# Ant.net
KiCad netlist of a schematic drawn in Altium Designer
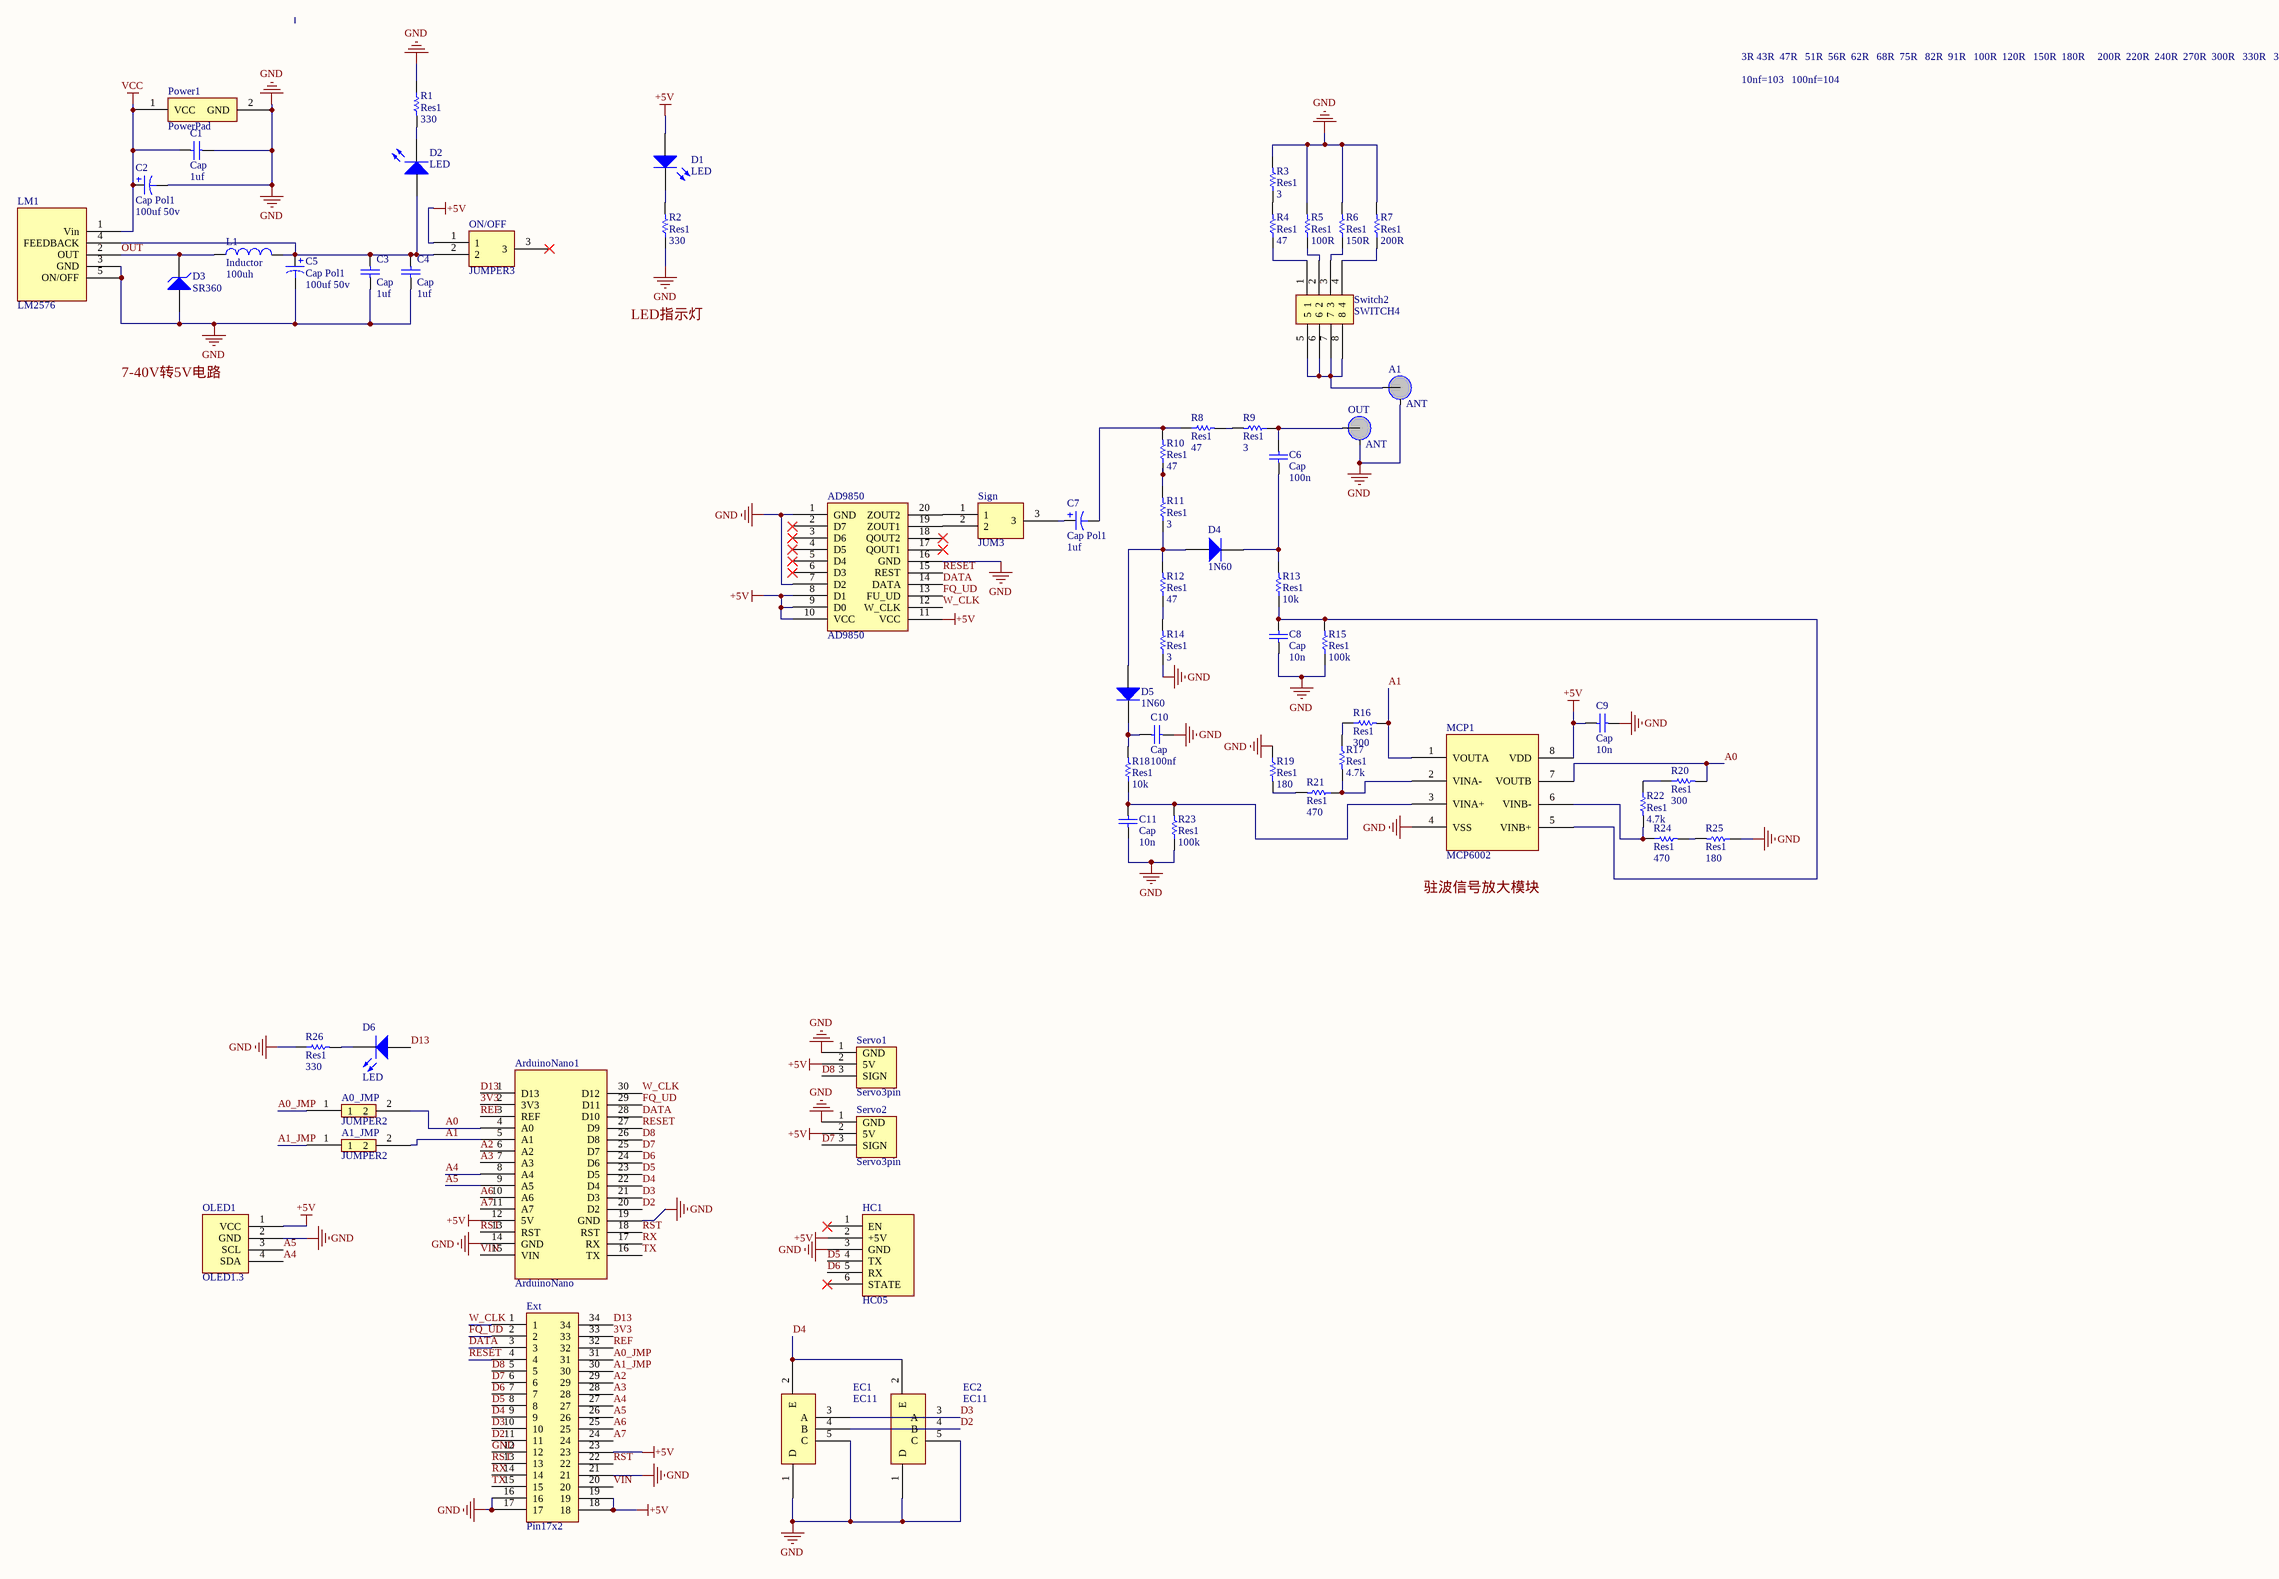
[diagram p0: Ant.SchDoc]

(export (version "E")
  (design (tool "Eeschema 10.0.6"))
  (components
    (comp (ref "A0_JMP") (value "JUMPER2") (footprint "PIN2") (libsource (lib "Ant") (part "JUMPER2")))
    (comp (ref "A1") (value "ANT") (footprint "SMA") (libsource (lib "Ant") (part "ANT")))
    (comp (ref "A1_JMP") (value "JUMPER2") (footprint "PIN2") (libsource (lib "Ant") (part "JUMPER2")))
    (comp (ref "AD9850") (value "AD9850") (footprint "AD9850") (libsource (lib "Ant") (part "AD9850")))
    (comp (ref "ArduinoNano1")
      (value "ArduinoNano")
      (footprint "ArduinoNano")
      (libsource (lib "Ant") (part "ArduinoNano"))
    )
    (comp (ref "C1")
      (value "Cap")
      (footprint "C0805")
      (description "Capacitor")
      (fields (field (name "ALTIUM_VALUE") "1uf") (field (name "PUBLISHER") "Altium Limited"))
      (libsource (lib "Miscellaneous Devices") (part "Cap"))
    )
    (comp (ref "C2")
      (value "Cap Pol1")
      (footprint "C08105")
      (description "Polarized Capacitor (Radial)")
      (fields (field (name "ALTIUM_VALUE") "100uf 50v") (field (name "PUBLISHER") "Altium Limited"))
      (libsource (lib "Miscellaneous Devices") (part "Cap Pol1"))
    )
    (comp (ref "C3")
      (value "Cap")
      (footprint "C0805")
      (description "Capacitor")
      (fields (field (name "ALTIUM_VALUE") "1uf") (field (name "PUBLISHER") "Altium Limited"))
      (libsource (lib "Miscellaneous Devices") (part "Cap"))
    )
    (comp (ref "C4")
      (value "Cap")
      (footprint "C0805")
      (description "Capacitor")
      (fields (field (name "ALTIUM_VALUE") "1uf") (field (name "PUBLISHER") "Altium Limited"))
      (libsource (lib "Miscellaneous Devices") (part "Cap"))
    )
    (comp (ref "C5")
      (value "Cap Pol1")
      (footprint "C08105")
      (description "Polarized Capacitor (Radial)")
      (fields (field (name "ALTIUM_VALUE") "100uf 50v") (field (name "PUBLISHER") "Altium Limited"))
      (libsource (lib "Miscellaneous Devices") (part "Cap Pol1"))
    )
    (comp (ref "C6")
      (value "Cap")
      (footprint "C1206")
      (description "Capacitor")
      (fields (field (name "ALTIUM_VALUE") "100n") (field (name "PUBLISHER") "Altium Limited"))
      (libsource (lib "Miscellaneous Devices") (part "Cap"))
    )
    (comp (ref "C7")
      (value "Cap Pol1")
      (footprint "C5X5.4")
      (description "Polarized Capacitor (Radial)")
      (fields (field (name "ALTIUM_VALUE") "1uf") (field (name "PUBLISHER") "Altium Limited"))
      (libsource (lib "Miscellaneous Devices") (part "Cap Pol1"))
    )
    (comp (ref "C8")
      (value "Cap")
      (footprint "C1206")
      (description "Capacitor")
      (fields (field (name "ALTIUM_VALUE") "10n") (field (name "PUBLISHER") "Altium Limited"))
      (libsource (lib "Miscellaneous Devices") (part "Cap"))
    )
    (comp (ref "C9")
      (value "Cap")
      (footprint "C1206")
      (description "Capacitor")
      (fields (field (name "ALTIUM_VALUE") "10n") (field (name "PUBLISHER") "Altium Limited"))
      (libsource (lib "Miscellaneous Devices") (part "Cap"))
    )
    (comp (ref "C10")
      (value "Cap")
      (footprint "C1206")
      (description "Capacitor")
      (fields (field (name "ALTIUM_VALUE") "100nf") (field (name "PUBLISHER") "Altium Limited"))
      (libsource (lib "Miscellaneous Devices") (part "Cap"))
    )
    (comp (ref "C11")
      (value "Cap")
      (footprint "C1206")
      (description "Capacitor")
      (fields (field (name "ALTIUM_VALUE") "10n") (field (name "PUBLISHER") "Altium Limited"))
      (libsource (lib "Miscellaneous Devices") (part "Cap"))
    )
    (comp (ref "D1")
      (value "LED")
      (footprint "LED0805")
      (description "Typical INFRARED GaAs LED")
      (fields (field (name "PUBLISHER") "Altium Limited"))
      (libsource (lib "Miscellaneous Devices") (part "LED0"))
    )
    (comp (ref "D2")
      (value "LED")
      (footprint "LED0805")
      (description "Typical INFRARED GaAs LED")
      (fields (field (name "PUBLISHER") "Altium Limited"))
      (libsource (lib "Miscellaneous Devices") (part "LED0"))
    )
    (comp (ref "D3")
      (value "SR360")
      (footprint "SR360")
      (description "Zener Diode")
      (fields (field (name "PUBLISHER") "Altium Limited"))
      (libsource (lib "Miscellaneous Devices") (part "D Zener"))
    )
    (comp (ref "D4")
      (value "1N60")
      (footprint "1N60")
      (description "Default Diode")
      (fields (field (name "PUBLISHER") "Altium Limited"))
      (libsource (lib "Miscellaneous Devices") (part "Diode"))
    )
    (comp (ref "D5")
      (value "1N60")
      (footprint "1N60")
      (description "Default Diode")
      (fields (field (name "PUBLISHER") "Altium Limited"))
      (libsource (lib "Miscellaneous Devices") (part "Diode"))
    )
    (comp (ref "D6")
      (value "LED")
      (footprint "LED0805")
      (description "Typical INFRARED GaAs LED")
      (fields (field (name "PUBLISHER") "Altium Limited"))
      (libsource (lib "Miscellaneous Devices") (part "LED0"))
    )
    (comp (ref "EC1") (value "EC11") (footprint "PIN5") (libsource (lib "Ant") (part "EC11")))
    (comp (ref "EC2") (value "EC11") (footprint "EC11") (libsource (lib "Ant") (part "EC11")))
    (comp (ref "Ext") (value "Pin17x2") (footprint "Pin17x2") (libsource (lib "Ant") (part "Pin17x2")))
    (comp (ref "HC1") (value "HC05") (footprint "PIN6") (libsource (lib "Ant") (part "HC05")))
    (comp (ref "L1")
      (value "Inductor")
      (footprint "L12127")
      (fields (field (name "ALTIUM_VALUE") "100uh") (field (name "PUBLISHER") "Altium Limited"))
      (libsource (lib "Miscellaneous Devices") (part "Inductor"))
    )
    (comp (ref "LM1") (value "LM2576") (libsource (lib "Ant") (part "LM2576")))
    (comp (ref "MCP1") (value "MCP6002") (footprint "MCP6002") (libsource (lib "Ant") (part "MCP6002")))
    (comp (ref "OLED1") (value "OLED1.3") (footprint "PIN4") (libsource (lib "Ant") (part "OLED1.3")))
    (comp (ref "ON/OFF") (value "JUMPER3") (footprint "SWITCH") (libsource (lib "Ant") (part "JUMPER3")))
    (comp (ref "OUT") (value "ANT") (footprint "PAD2") (libsource (lib "Ant") (part "ANT")))
    (comp (ref "Power1") (value "PowerPad") (footprint "Power3pin") (libsource (lib "Ant") (part "PowerPad")))
    (comp (ref "R1")
      (value "Res1")
      (footprint "r0805")
      (description "Resistor")
      (fields (field (name "ALTIUM_VALUE") "330") (field (name "PUBLISHER") "Altium Limited"))
      (libsource (lib "Miscellaneous Devices") (part "Res1"))
    )
    (comp (ref "R2")
      (value "Res1")
      (footprint "r0805")
      (description "Resistor")
      (fields (field (name "ALTIUM_VALUE") "330") (field (name "PUBLISHER") "Altium Limited"))
      (libsource (lib "Miscellaneous Devices") (part "Res1"))
    )
    (comp (ref "R3")
      (value "Res1")
      (footprint "R1206")
      (description "Resistor")
      (fields (field (name "ALTIUM_VALUE") "3") (field (name "PUBLISHER") "Altium Limited"))
      (libsource (lib "Miscellaneous Devices") (part "Res1"))
    )
    (comp (ref "R4")
      (value "Res1")
      (footprint "R1206")
      (description "Resistor")
      (fields (field (name "ALTIUM_VALUE") "47") (field (name "PUBLISHER") "Altium Limited"))
      (libsource (lib "Miscellaneous Devices") (part "Res1"))
    )
    (comp (ref "R5")
      (value "Res1")
      (footprint "R1206")
      (description "Resistor")
      (fields (field (name "ALTIUM_VALUE") "100R") (field (name "PUBLISHER") "Altium Limited"))
      (libsource (lib "Miscellaneous Devices") (part "Res1"))
    )
    (comp (ref "R6")
      (value "Res1")
      (footprint "R1206")
      (description "Resistor")
      (fields (field (name "ALTIUM_VALUE") "150R") (field (name "PUBLISHER") "Altium Limited"))
      (libsource (lib "Miscellaneous Devices") (part "Res1"))
    )
    (comp (ref "R7")
      (value "Res1")
      (footprint "R1206")
      (description "Resistor")
      (fields (field (name "ALTIUM_VALUE") "200R") (field (name "PUBLISHER") "Altium Limited"))
      (libsource (lib "Miscellaneous Devices") (part "Res1"))
    )
    (comp (ref "R8")
      (value "Res1")
      (footprint "R1206")
      (description "Resistor")
      (fields (field (name "ALTIUM_VALUE") "47") (field (name "PUBLISHER") "Altium Limited"))
      (libsource (lib "Miscellaneous Devices") (part "Res1"))
    )
    (comp (ref "R9")
      (value "Res1")
      (footprint "R1206")
      (description "Resistor")
      (fields (field (name "ALTIUM_VALUE") "3") (field (name "PUBLISHER") "Altium Limited"))
      (libsource (lib "Miscellaneous Devices") (part "Res1"))
    )
    (comp (ref "R10")
      (value "Res1")
      (footprint "R1206")
      (description "Resistor")
      (fields (field (name "ALTIUM_VALUE") "47") (field (name "PUBLISHER") "Altium Limited"))
      (libsource (lib "Miscellaneous Devices") (part "Res1"))
    )
    (comp (ref "R11")
      (value "Res1")
      (footprint "R1206")
      (description "Resistor")
      (fields (field (name "ALTIUM_VALUE") "3") (field (name "PUBLISHER") "Altium Limited"))
      (libsource (lib "Miscellaneous Devices") (part "Res1"))
    )
    (comp (ref "R12")
      (value "Res1")
      (footprint "R1206")
      (description "Resistor")
      (fields (field (name "ALTIUM_VALUE") "47") (field (name "PUBLISHER") "Altium Limited"))
      (libsource (lib "Miscellaneous Devices") (part "Res1"))
    )
    (comp (ref "R13")
      (value "Res1")
      (footprint "R1206")
      (description "Resistor")
      (fields (field (name "ALTIUM_VALUE") "10k") (field (name "PUBLISHER") "Altium Limited"))
      (libsource (lib "Miscellaneous Devices") (part "Res1"))
    )
    (comp (ref "R14")
      (value "Res1")
      (footprint "R1206")
      (description "Resistor")
      (fields (field (name "ALTIUM_VALUE") "3") (field (name "PUBLISHER") "Altium Limited"))
      (libsource (lib "Miscellaneous Devices") (part "Res1"))
    )
    (comp (ref "R15")
      (value "Res1")
      (footprint "R1206")
      (description "Resistor")
      (fields (field (name "ALTIUM_VALUE") "100k") (field (name "PUBLISHER") "Altium Limited"))
      (libsource (lib "Miscellaneous Devices") (part "Res1"))
    )
    (comp (ref "R16")
      (value "Res1")
      (footprint "R1206")
      (description "Resistor")
      (fields (field (name "ALTIUM_VALUE") "300") (field (name "PUBLISHER") "Altium Limited"))
      (libsource (lib "Miscellaneous Devices") (part "Res1"))
    )
    (comp (ref "R17")
      (value "Res1")
      (footprint "R1206")
      (description "Resistor")
      (fields (field (name "ALTIUM_VALUE") "4.7k") (field (name "PUBLISHER") "Altium Limited"))
      (libsource (lib "Miscellaneous Devices") (part "Res1"))
    )
    (comp (ref "R18")
      (value "Res1")
      (footprint "R1206")
      (description "Resistor")
      (fields (field (name "ALTIUM_VALUE") "10k") (field (name "PUBLISHER") "Altium Limited"))
      (libsource (lib "Miscellaneous Devices") (part "Res1"))
    )
    (comp (ref "R19")
      (value "Res1")
      (footprint "R1206")
      (description "Resistor")
      (fields (field (name "ALTIUM_VALUE") "180") (field (name "PUBLISHER") "Altium Limited"))
      (libsource (lib "Miscellaneous Devices") (part "Res1"))
    )
    (comp (ref "R20")
      (value "Res1")
      (footprint "R1206")
      (description "Resistor")
      (fields (field (name "ALTIUM_VALUE") "300") (field (name "PUBLISHER") "Altium Limited"))
      (libsource (lib "Miscellaneous Devices") (part "Res1"))
    )
    (comp (ref "R21")
      (value "Res1")
      (footprint "R1206")
      (description "Resistor")
      (fields (field (name "ALTIUM_VALUE") "470") (field (name "PUBLISHER") "Altium Limited"))
      (libsource (lib "Miscellaneous Devices") (part "Res1"))
    )
    (comp (ref "R22")
      (value "Res1")
      (footprint "R1206")
      (description "Resistor")
      (fields (field (name "ALTIUM_VALUE") "4.7k") (field (name "PUBLISHER") "Altium Limited"))
      (libsource (lib "Miscellaneous Devices") (part "Res1"))
    )
    (comp (ref "R23")
      (value "Res1")
      (footprint "R1206")
      (description "Resistor")
      (fields (field (name "ALTIUM_VALUE") "100k") (field (name "PUBLISHER") "Altium Limited"))
      (libsource (lib "Miscellaneous Devices") (part "Res1"))
    )
    (comp (ref "R24")
      (value "Res1")
      (footprint "R1206")
      (description "Resistor")
      (fields (field (name "ALTIUM_VALUE") "470") (field (name "PUBLISHER") "Altium Limited"))
      (libsource (lib "Miscellaneous Devices") (part "Res1"))
    )
    (comp (ref "R25")
      (value "Res1")
      (footprint "R1206")
      (description "Resistor")
      (fields (field (name "ALTIUM_VALUE") "180") (field (name "PUBLISHER") "Altium Limited"))
      (libsource (lib "Miscellaneous Devices") (part "Res1"))
    )
    (comp (ref "R26")
      (value "Res1")
      (footprint "r0805")
      (description "Resistor")
      (fields (field (name "ALTIUM_VALUE") "330") (field (name "PUBLISHER") "Altium Limited"))
      (libsource (lib "Miscellaneous Devices") (part "Res1"))
    )
    (comp (ref "Servo1") (value "Servo3pin") (footprint "PIN3") (libsource (lib "Ant") (part "Servo3pin")))
    (comp (ref "Servo2") (value "Servo3pin") (footprint "PIN3") (libsource (lib "Ant") (part "Servo3pin")))
    (comp (ref "Sign") (value "JUM3") (footprint "SWITCH3") (libsource (lib "Ant") (part "JUM3")))
    (comp (ref "Switch2") (value "SWITCH4") (footprint "SWITCH4") (libsource (lib "Ant") (part "SWITCH4")))
  )
  (nets
    (net (code "1") (name "+5V") (class "Default")
      (node (ref "AD9850") (pin "10") (pinfunction "VCC_10") (pintype "passive"))
      (node (ref "AD9850") (pin "11") (pinfunction "VCC_11") (pintype "passive"))
      (node (ref "AD9850") (pin "8") (pinfunction "D1_8") (pintype "passive"))
      (node (ref "AD9850") (pin "9") (pinfunction "D0_9") (pintype "passive"))
      (node (ref "ArduinoNano1") (pin "12") (pinfunction "5V_12") (pintype "passive"))
      (node (ref "C9") (pin "1") (pinfunction "1_1") (pintype "passive"))
      (node (ref "D1") (pin "1") (pinfunction "A_1") (pintype "passive"))
      (node (ref "Ext") (pin "18") (pinfunction "18_18") (pintype "passive"))
      (node (ref "Ext") (pin "19") (pinfunction "19_19") (pintype "passive"))
      (node (ref "Ext") (pin "23") (pinfunction "23_23") (pintype "passive"))
      (node (ref "HC1") (pin "2") (pinfunction "+5V_2") (pintype "passive"))
      (node (ref "MCP1") (pin "8") (pinfunction "VDD_8") (pintype "passive"))
      (node (ref "OLED1") (pin "1") (pinfunction "VCC_1") (pintype "passive"))
      (node (ref "ON/OFF") (pin "1") (pinfunction "1_1") (pintype "passive"))
      (node (ref "Servo1") (pin "2") (pinfunction "5V_2") (pintype "passive"))
      (node (ref "Servo2") (pin "2") (pinfunction "5V_2") (pintype "passive"))
    )
    (net (code "2") (name "/3V3") (class "Default")
      (node (ref "ArduinoNano1") (pin "2") (pinfunction "3V3_2") (pintype "passive"))
      (node (ref "Ext") (pin "33") (pinfunction "33_33") (pintype "passive"))
    )
    (net (code "3") (name "/A0") (class "Default")
      (node (ref "A0_JMP") (pin "2") (pinfunction "2_2") (pintype "passive"))
      (node (ref "ArduinoNano1") (pin "4") (pinfunction "A0_4") (pintype "passive"))
      (node (ref "MCP1") (pin "7") (pinfunction "VOUTB_7") (pintype "passive"))
      (node (ref "R20") (pin "2") (pinfunction "2_2") (pintype "passive"))
    )
    (net (code "4") (name "/A0_JMP") (class "Default")
      (node (ref "A0_JMP") (pin "1") (pinfunction "1_1") (pintype "passive"))
      (node (ref "Ext") (pin "31") (pinfunction "31_31") (pintype "passive"))
    )
    (net (code "5") (name "/A1") (class "Default")
      (node (ref "A1_JMP") (pin "2") (pinfunction "2_2") (pintype "passive"))
      (node (ref "ArduinoNano1") (pin "5") (pinfunction "A1_5") (pintype "passive"))
      (node (ref "MCP1") (pin "1") (pinfunction "VOUTA_1") (pintype "passive"))
      (node (ref "R16") (pin "2") (pinfunction "2_2") (pintype "passive"))
    )
    (net (code "6") (name "/A1_JMP") (class "Default")
      (node (ref "A1_JMP") (pin "1") (pinfunction "1_1") (pintype "passive"))
      (node (ref "Ext") (pin "30") (pinfunction "30_30") (pintype "passive"))
    )
    (net (code "7") (name "/A2") (class "Default")
      (node (ref "ArduinoNano1") (pin "6") (pinfunction "A2_6") (pintype "passive"))
      (node (ref "Ext") (pin "29") (pinfunction "29_29") (pintype "passive"))
    )
    (net (code "8") (name "/A3") (class "Default")
      (node (ref "ArduinoNano1") (pin "7") (pinfunction "A3_7") (pintype "passive"))
      (node (ref "Ext") (pin "28") (pinfunction "28_28") (pintype "passive"))
    )
    (net (code "9") (name "/A4") (class "Default")
      (node (ref "ArduinoNano1") (pin "8") (pinfunction "A4_8") (pintype "passive"))
      (node (ref "Ext") (pin "27") (pinfunction "27_27") (pintype "passive"))
      (node (ref "OLED1") (pin "4") (pinfunction "SDA_4") (pintype "passive"))
    )
    (net (code "10") (name "/A5") (class "Default")
      (node (ref "ArduinoNano1") (pin "9") (pinfunction "A5_9") (pintype "passive"))
      (node (ref "Ext") (pin "26") (pinfunction "26_26") (pintype "passive"))
      (node (ref "OLED1") (pin "3") (pinfunction "SCL_3") (pintype "passive"))
    )
    (net (code "11") (name "/A6") (class "Default")
      (node (ref "ArduinoNano1") (pin "10") (pinfunction "A6_10") (pintype "passive"))
      (node (ref "Ext") (pin "25") (pinfunction "25_25") (pintype "passive"))
    )
    (net (code "12") (name "/A7") (class "Default")
      (node (ref "ArduinoNano1") (pin "11") (pinfunction "A7_11") (pintype "passive"))
      (node (ref "Ext") (pin "24") (pinfunction "24_24") (pintype "passive"))
    )
    (net (code "13") (name "/D2") (class "Default")
      (node (ref "ArduinoNano1") (pin "20") (pinfunction "D2_20") (pintype "passive"))
      (node (ref "EC1") (pin "4") (pinfunction "B_4") (pintype "passive"))
      (node (ref "EC2") (pin "4") (pinfunction "B_4") (pintype "passive"))
      (node (ref "Ext") (pin "11") (pinfunction "11_11") (pintype "passive"))
    )
    (net (code "14") (name "/D3") (class "Default")
      (node (ref "ArduinoNano1") (pin "21") (pinfunction "D3_21") (pintype "passive"))
      (node (ref "EC1") (pin "3") (pinfunction "A_3") (pintype "passive"))
      (node (ref "EC2") (pin "3") (pinfunction "A_3") (pintype "passive"))
      (node (ref "Ext") (pin "10") (pinfunction "10_10") (pintype "passive"))
    )
    (net (code "15") (name "/D4") (class "Default")
      (node (ref "ArduinoNano1") (pin "22") (pinfunction "D4_22") (pintype "passive"))
      (node (ref "EC1") (pin "2") (pinfunction "E_2") (pintype "passive"))
      (node (ref "EC2") (pin "2") (pinfunction "E_2") (pintype "passive"))
      (node (ref "Ext") (pin "9") (pinfunction "9_9") (pintype "passive"))
    )
    (net (code "16") (name "/D5") (class "Default")
      (node (ref "ArduinoNano1") (pin "23") (pinfunction "D5_23") (pintype "passive"))
      (node (ref "Ext") (pin "8") (pinfunction "8_8") (pintype "passive"))
      (node (ref "HC1") (pin "4") (pinfunction "TX_4") (pintype "passive"))
    )
    (net (code "17") (name "/D6") (class "Default")
      (node (ref "ArduinoNano1") (pin "24") (pinfunction "D6_24") (pintype "passive"))
      (node (ref "Ext") (pin "7") (pinfunction "7_7") (pintype "passive"))
      (node (ref "HC1") (pin "5") (pinfunction "RX_5") (pintype "passive"))
    )
    (net (code "18") (name "/D7") (class "Default")
      (node (ref "ArduinoNano1") (pin "25") (pinfunction "D7_25") (pintype "passive"))
      (node (ref "Ext") (pin "6") (pinfunction "6_6") (pintype "passive"))
      (node (ref "Servo2") (pin "3") (pinfunction "SIGN_3") (pintype "passive"))
    )
    (net (code "19") (name "/D8") (class "Default")
      (node (ref "ArduinoNano1") (pin "26") (pinfunction "D8_26") (pintype "passive"))
      (node (ref "Ext") (pin "5") (pinfunction "5_5") (pintype "passive"))
      (node (ref "Servo1") (pin "3") (pinfunction "SIGN_3") (pintype "passive"))
    )
    (net (code "20") (name "/D13") (class "Default")
      (node (ref "ArduinoNano1") (pin "1") (pinfunction "D13_1") (pintype "passive"))
      (node (ref "D6") (pin "1") (pinfunction "A_1") (pintype "passive"))
      (node (ref "Ext") (pin "34") (pinfunction "34_34") (pintype "passive"))
    )
    (net (code "21") (name "/DATA") (class "Default")
      (node (ref "AD9850") (pin "14") (pinfunction "DATA_14") (pintype "passive"))
      (node (ref "ArduinoNano1") (pin "28") (pinfunction "D10_28") (pintype "passive"))
      (node (ref "Ext") (pin "3") (pinfunction "3_3") (pintype "passive"))
    )
    (net (code "22") (name "/FQ_UD") (class "Default")
      (node (ref "AD9850") (pin "13") (pinfunction "FU_UD_13") (pintype "passive"))
      (node (ref "ArduinoNano1") (pin "29") (pinfunction "D11_29") (pintype "passive"))
      (node (ref "Ext") (pin "2") (pinfunction "2_2") (pintype "passive"))
    )
    (net (code "23") (name "/OUT") (class "Default")
      (node (ref "D3") (pin "2") (pinfunction "K_2") (pintype "passive"))
      (node (ref "L1") (pin "1") (pinfunction "1_1") (pintype "passive"))
      (node (ref "LM1") (pin "2") (pinfunction "OUT_2") (pintype "passive"))
    )
    (net (code "24") (name "/REF") (class "Default")
      (node (ref "ArduinoNano1") (pin "3") (pinfunction "REF_3") (pintype "passive"))
      (node (ref "Ext") (pin "32") (pinfunction "32_32") (pintype "passive"))
    )
    (net (code "25") (name "/RESET") (class "Default")
      (node (ref "AD9850") (pin "15") (pinfunction "REST_15") (pintype "passive"))
      (node (ref "ArduinoNano1") (pin "27") (pinfunction "D9_27") (pintype "passive"))
      (node (ref "Ext") (pin "4") (pinfunction "4_4") (pintype "passive"))
    )
    (net (code "26") (name "/RST") (class "Default")
      (node (ref "ArduinoNano1") (pin "13") (pinfunction "RST_13") (pintype "passive"))
      (node (ref "ArduinoNano1") (pin "18") (pinfunction "RST_18") (pintype "passive"))
      (node (ref "Ext") (pin "13") (pinfunction "13_13") (pintype "passive"))
      (node (ref "Ext") (pin "22") (pinfunction "22_22") (pintype "passive"))
    )
    (net (code "27") (name "/RX") (class "Default")
      (node (ref "ArduinoNano1") (pin "17") (pinfunction "RX_17") (pintype "passive"))
      (node (ref "Ext") (pin "14") (pinfunction "14_14") (pintype "passive"))
    )
    (net (code "28") (name "/TX") (class "Default")
      (node (ref "ArduinoNano1") (pin "16") (pinfunction "TX_16") (pintype "passive"))
      (node (ref "Ext") (pin "15") (pinfunction "15_15") (pintype "passive"))
    )
    (net (code "29") (name "/VIN") (class "Default")
      (node (ref "ArduinoNano1") (pin "15") (pinfunction "VIN_15") (pintype "passive"))
      (node (ref "Ext") (pin "20") (pinfunction "20_20") (pintype "passive"))
    )
    (net (code "30") (name "/W_CLK") (class "Default")
      (node (ref "AD9850") (pin "12") (pinfunction "W_CLK_12") (pintype "passive"))
      (node (ref "ArduinoNano1") (pin "30") (pinfunction "D12_30") (pintype "passive"))
      (node (ref "Ext") (pin "1") (pinfunction "1_1") (pintype "passive"))
    )
    (net (code "31") (name "GND") (class "Default")
      (node (ref "A1") (pin "2") (pintype "passive"))
      (node (ref "AD9850") (pin "1") (pinfunction "GND_1") (pintype "passive"))
      (node (ref "AD9850") (pin "16") (pinfunction "GND_16") (pintype "passive"))
      (node (ref "AD9850") (pin "7") (pinfunction "D2_7") (pintype "passive"))
      (node (ref "ArduinoNano1") (pin "14") (pinfunction "GND_14") (pintype "passive"))
      (node (ref "ArduinoNano1") (pin "19") (pinfunction "GND_19") (pintype "passive"))
      (node (ref "C1") (pin "2") (pinfunction "2_2") (pintype "passive"))
      (node (ref "C10") (pin "2") (pinfunction "2_2") (pintype "passive"))
      (node (ref "C11") (pin "1") (pinfunction "1_1") (pintype "passive"))
      (node (ref "C2") (pin "2") (pinfunction "2_2") (pintype "passive"))
      (node (ref "C3") (pin "2") (pinfunction "2_2") (pintype "passive"))
      (node (ref "C4") (pin "2") (pinfunction "2_2") (pintype "passive"))
      (node (ref "C5") (pin "2") (pinfunction "2_2") (pintype "passive"))
      (node (ref "C8") (pin "2") (pinfunction "2_2") (pintype "passive"))
      (node (ref "C9") (pin "2") (pinfunction "2_2") (pintype "passive"))
      (node (ref "D3") (pin "1") (pinfunction "A_1") (pintype "passive"))
      (node (ref "EC1") (pin "1") (pinfunction "D_1") (pintype "passive"))
      (node (ref "EC1") (pin "5") (pinfunction "C_5") (pintype "passive"))
      (node (ref "EC2") (pin "1") (pinfunction "D_1") (pintype "passive"))
      (node (ref "EC2") (pin "5") (pinfunction "C_5") (pintype "passive"))
      (node (ref "Ext") (pin "12") (pinfunction "12_12") (pintype "passive"))
      (node (ref "Ext") (pin "16") (pinfunction "16_16") (pintype "passive"))
      (node (ref "Ext") (pin "17") (pinfunction "17_17") (pintype "passive"))
      (node (ref "Ext") (pin "21") (pinfunction "21_21") (pintype "passive"))
      (node (ref "HC1") (pin "3") (pinfunction "GND_3") (pintype "passive"))
      (node (ref "LM1") (pin "3") (pinfunction "GND_3") (pintype "passive"))
      (node (ref "LM1") (pin "5") (pinfunction "ON/OFF_5") (pintype "passive"))
      (node (ref "MCP1") (pin "4") (pinfunction "VSS_4") (pintype "passive"))
      (node (ref "OLED1") (pin "2") (pinfunction "GND_2") (pintype "passive"))
      (node (ref "OUT") (pin "2") (pintype "passive"))
      (node (ref "Power1") (pin "2") (pinfunction "GND_2") (pintype "passive"))
      (node (ref "R1") (pin "1") (pinfunction "1_1") (pintype "passive"))
      (node (ref "R14") (pin "1") (pinfunction "1_1") (pintype "passive"))
      (node (ref "R15") (pin "1") (pinfunction "1_1") (pintype "passive"))
      (node (ref "R19") (pin "1") (pinfunction "1_1") (pintype "passive"))
      (node (ref "R2") (pin "1") (pinfunction "1_1") (pintype "passive"))
      (node (ref "R23") (pin "1") (pinfunction "1_1") (pintype "passive"))
      (node (ref "R25") (pin "1") (pinfunction "1_1") (pintype "passive"))
      (node (ref "R26") (pin "1") (pinfunction "1_1") (pintype "passive"))
      (node (ref "R3") (pin "2") (pinfunction "2_2") (pintype "passive"))
      (node (ref "R5") (pin "2") (pinfunction "2_2") (pintype "passive"))
      (node (ref "R6") (pin "2") (pinfunction "2_2") (pintype "passive"))
      (node (ref "R7") (pin "2") (pinfunction "2_2") (pintype "passive"))
      (node (ref "Servo1") (pin "1") (pinfunction "GND_1") (pintype "passive"))
      (node (ref "Servo2") (pin "1") (pinfunction "GND_1") (pintype "passive"))
    )
    (net (code "32") (name "Net-(A1-Pad1)") (class "Default")
      (node (ref "A1") (pin "1") (pintype "passive"))
      (node (ref "Switch2") (pin "5") (pinfunction "5_5") (pintype "passive"))
      (node (ref "Switch2") (pin "6") (pinfunction "6_6") (pintype "passive"))
      (node (ref "Switch2") (pin "7") (pinfunction "7_7") (pintype "passive"))
      (node (ref "Switch2") (pin "8") (pinfunction "8_8") (pintype "passive"))
    )
    (net (code "33") (name "Net-(AD9850-ZOUT1)") (class "Default")
      (node (ref "AD9850") (pin "19") (pinfunction "ZOUT1_19") (pintype "passive"))
      (node (ref "Sign") (pin "2") (pinfunction "2_2") (pintype "passive"))
    )
    (net (code "34") (name "Net-(AD9850-ZOUT2)") (class "Default")
      (node (ref "AD9850") (pin "20") (pinfunction "ZOUT2_20") (pintype "passive"))
      (node (ref "Sign") (pin "1") (pinfunction "1_1") (pintype "passive"))
    )
    (net (code "35") (name "Net-(C6-Pad1)") (class "Default")
      (node (ref "C6") (pin "1") (pinfunction "1_1") (pintype "passive"))
      (node (ref "OUT") (pin "1") (pintype "passive"))
      (node (ref "R9") (pin "1") (pinfunction "1_1") (pintype "passive"))
    )
    (net (code "36") (name "Net-(C7-Pad1)") (class "Default")
      (node (ref "C7") (pin "1") (pinfunction "1_1") (pintype "passive"))
      (node (ref "Sign") (pin "3") (pinfunction "3_3") (pintype "passive"))
    )
    (net (code "37") (name "Net-(C7-Pad2)") (class "Default")
      (node (ref "C7") (pin "2") (pinfunction "2_2") (pintype "passive"))
      (node (ref "R10") (pin "2") (pinfunction "2_2") (pintype "passive"))
      (node (ref "R8") (pin "1") (pinfunction "1_1") (pintype "passive"))
    )
    (net (code "38") (name "Net-(D1-K)") (class "Default")
      (node (ref "D1") (pin "2") (pinfunction "K_2") (pintype "passive"))
      (node (ref "R2") (pin "2") (pinfunction "2_2") (pintype "passive"))
    )
    (net (code "39") (name "Net-(D2-A)") (class "Default")
      (node (ref "C3") (pin "1") (pinfunction "1_1") (pintype "passive"))
      (node (ref "C4") (pin "1") (pinfunction "1_1") (pintype "passive"))
      (node (ref "C5") (pin "1") (pinfunction "1_1") (pintype "passive"))
      (node (ref "D2") (pin "1") (pinfunction "A_1") (pintype "passive"))
      (node (ref "L1") (pin "2") (pinfunction "2_2") (pintype "passive"))
      (node (ref "LM1") (pin "4") (pinfunction "FEEDBACK_4") (pintype "passive"))
      (node (ref "ON/OFF") (pin "2") (pinfunction "2_2") (pintype "passive"))
    )
    (net (code "40") (name "Net-(D2-K)") (class "Default")
      (node (ref "D2") (pin "2") (pinfunction "K_2") (pintype "passive"))
      (node (ref "R1") (pin "2") (pinfunction "2_2") (pintype "passive"))
    )
    (net (code "41") (name "Net-(D4-A)") (class "Default")
      (node (ref "D4") (pin "1") (pinfunction "A_1") (pintype "passive"))
      (node (ref "D5") (pin "1") (pinfunction "A_1") (pintype "passive"))
      (node (ref "R11") (pin "1") (pinfunction "1_1") (pintype "passive"))
      (node (ref "R12") (pin "2") (pinfunction "2_2") (pintype "passive"))
    )
    (net (code "42") (name "Net-(D4-K)") (class "Default")
      (node (ref "C6") (pin "2") (pinfunction "2_2") (pintype "passive"))
      (node (ref "D4") (pin "2") (pinfunction "K_2") (pintype "passive"))
      (node (ref "R13") (pin "2") (pinfunction "2_2") (pintype "passive"))
    )
    (net (code "43") (name "Net-(D5-K)") (class "Default")
      (node (ref "C10") (pin "1") (pinfunction "1_1") (pintype "passive"))
      (node (ref "D5") (pin "2") (pinfunction "K_2") (pintype "passive"))
      (node (ref "R18") (pin "2") (pinfunction "2_2") (pintype "passive"))
    )
    (net (code "44") (name "Net-(D6-K)") (class "Default")
      (node (ref "D6") (pin "2") (pinfunction "K_2") (pintype "passive"))
      (node (ref "R26") (pin "2") (pinfunction "2_2") (pintype "passive"))
    )
    (net (code "45") (name "Net-(MCP1-VINA+)") (class "Default")
      (node (ref "C11") (pin "2") (pinfunction "2_2") (pintype "passive"))
      (node (ref "MCP1") (pin "3") (pinfunction "VINA+_3") (pintype "passive"))
      (node (ref "R18") (pin "1") (pinfunction "1_1") (pintype "passive"))
      (node (ref "R23") (pin "2") (pinfunction "2_2") (pintype "passive"))
    )
    (net (code "46") (name "Net-(MCP1-VINA-)") (class "Default")
      (node (ref "MCP1") (pin "2") (pinfunction "VINA-_2") (pintype "passive"))
      (node (ref "R17") (pin "2") (pinfunction "2_2") (pintype "passive"))
      (node (ref "R21") (pin "1") (pinfunction "1_1") (pintype "passive"))
    )
    (net (code "47") (name "Net-(MCP1-VINB+)") (class "Default")
      (node (ref "C8") (pin "1") (pinfunction "1_1") (pintype "passive"))
      (node (ref "MCP1") (pin "5") (pinfunction "VINB+_5") (pintype "passive"))
      (node (ref "R13") (pin "1") (pinfunction "1_1") (pintype "passive"))
      (node (ref "R15") (pin "2") (pinfunction "2_2") (pintype "passive"))
    )
    (net (code "48") (name "Net-(MCP1-VINB-)") (class "Default")
      (node (ref "MCP1") (pin "6") (pinfunction "VINB-_6") (pintype "passive"))
      (node (ref "R22") (pin "2") (pinfunction "2_2") (pintype "passive"))
      (node (ref "R24") (pin "1") (pinfunction "1_1") (pintype "passive"))
    )
    (net (code "49") (name "Net-(R3-Pad1)") (class "Default")
      (node (ref "R3") (pin "1") (pinfunction "1_1") (pintype "passive"))
      (node (ref "R4") (pin "2") (pinfunction "2_2") (pintype "passive"))
    )
    (net (code "50") (name "Net-(R4-Pad1)") (class "Default")
      (node (ref "R4") (pin "1") (pinfunction "1_1") (pintype "passive"))
      (node (ref "Switch2") (pin "1") (pinfunction "1_1") (pintype "passive"))
    )
    (net (code "51") (name "Net-(R5-Pad1)") (class "Default")
      (node (ref "R5") (pin "1") (pinfunction "1_1") (pintype "passive"))
      (node (ref "Switch2") (pin "2") (pinfunction "2_2") (pintype "passive"))
    )
    (net (code "52") (name "Net-(R6-Pad1)") (class "Default")
      (node (ref "R6") (pin "1") (pinfunction "1_1") (pintype "passive"))
      (node (ref "Switch2") (pin "3") (pinfunction "3_3") (pintype "passive"))
    )
    (net (code "53") (name "Net-(R7-Pad1)") (class "Default")
      (node (ref "R7") (pin "1") (pinfunction "1_1") (pintype "passive"))
      (node (ref "Switch2") (pin "4") (pinfunction "4_4") (pintype "passive"))
    )
    (net (code "54") (name "Net-(R8-Pad2)") (class "Default")
      (node (ref "R8") (pin "2") (pinfunction "2_2") (pintype "passive"))
      (node (ref "R9") (pin "2") (pinfunction "2_2") (pintype "passive"))
    )
    (net (code "55") (name "Net-(R10-Pad1)") (class "Default")
      (node (ref "R10") (pin "1") (pinfunction "1_1") (pintype "passive"))
      (node (ref "R11") (pin "2") (pinfunction "2_2") (pintype "passive"))
    )
    (net (code "56") (name "Net-(R12-Pad1)") (class "Default")
      (node (ref "R12") (pin "1") (pinfunction "1_1") (pintype "passive"))
      (node (ref "R14") (pin "2") (pinfunction "2_2") (pintype "passive"))
    )
    (net (code "57") (name "Net-(R16-Pad1)") (class "Default")
      (node (ref "R16") (pin "1") (pinfunction "1_1") (pintype "passive"))
      (node (ref "R17") (pin "1") (pinfunction "1_1") (pintype "passive"))
    )
    (net (code "58") (name "Net-(R19-Pad2)") (class "Default")
      (node (ref "R19") (pin "2") (pinfunction "2_2") (pintype "passive"))
      (node (ref "R21") (pin "2") (pinfunction "2_2") (pintype "passive"))
    )
    (net (code "59") (name "Net-(R20-Pad1)") (class "Default")
      (node (ref "R20") (pin "1") (pinfunction "1_1") (pintype "passive"))
      (node (ref "R22") (pin "1") (pinfunction "1_1") (pintype "passive"))
    )
    (net (code "60") (name "Net-(R24-Pad2)") (class "Default")
      (node (ref "R24") (pin "2") (pinfunction "2_2") (pintype "passive"))
      (node (ref "R25") (pin "2") (pinfunction "2_2") (pintype "passive"))
    )
    (net (code "61") (name "VCC") (class "Default")
      (node (ref "C1") (pin "1") (pinfunction "1_1") (pintype "passive"))
      (node (ref "C2") (pin "1") (pinfunction "1_1") (pintype "passive"))
      (node (ref "LM1") (pin "1") (pinfunction "Vin_1") (pintype "passive"))
      (node (ref "Power1") (pin "1") (pinfunction "VCC_1") (pintype "passive"))
    )
    (net (code "62") (name "unconnected-(AD9850-D3-Pad6)") (class "Default")
      (node (ref "AD9850") (pin "6") (pinfunction "D3_6") (pintype "passive+no_connect"))
    )
    (net (code "63") (name "unconnected-(AD9850-D4-Pad5)") (class "Default")
      (node (ref "AD9850") (pin "5") (pinfunction "D4_5") (pintype "passive+no_connect"))
    )
    (net (code "64") (name "unconnected-(AD9850-D5-Pad4)") (class "Default")
      (node (ref "AD9850") (pin "4") (pinfunction "D5_4") (pintype "passive+no_connect"))
    )
    (net (code "65") (name "unconnected-(AD9850-D6-Pad3)") (class "Default")
      (node (ref "AD9850") (pin "3") (pinfunction "D6_3") (pintype "passive+no_connect"))
    )
    (net (code "66") (name "unconnected-(AD9850-D7-Pad2)") (class "Default")
      (node (ref "AD9850") (pin "2") (pinfunction "D7_2") (pintype "passive+no_connect"))
    )
    (net (code "67") (name "unconnected-(AD9850-QOUT1-Pad17)") (class "Default")
      (node (ref "AD9850") (pin "17") (pinfunction "QOUT1_17") (pintype "passive+no_connect"))
    )
    (net (code "68") (name "unconnected-(AD9850-QOUT2-Pad18)") (class "Default")
      (node (ref "AD9850") (pin "18") (pinfunction "QOUT2_18") (pintype "passive+no_connect"))
    )
    (net (code "69") (name "unconnected-(HC1-EN-Pad1)") (class "Default")
      (node (ref "HC1") (pin "1") (pinfunction "EN_1") (pintype "passive+no_connect"))
    )
    (net (code "70") (name "unconnected-(HC1-STATE-Pad6)") (class "Default")
      (node (ref "HC1") (pin "6") (pinfunction "STATE_6") (pintype "passive+no_connect"))
    )
    (net (code "71") (name "unconnected-(ON/OFF-Pad3)") (class "Default")
      (node (ref "ON/OFF") (pin "3") (pinfunction "3_3") (pintype "passive+no_connect"))
    )
  )
)
